# LEDMatrix.net
KiCad netlist of a schematic drawn in Altium Designer
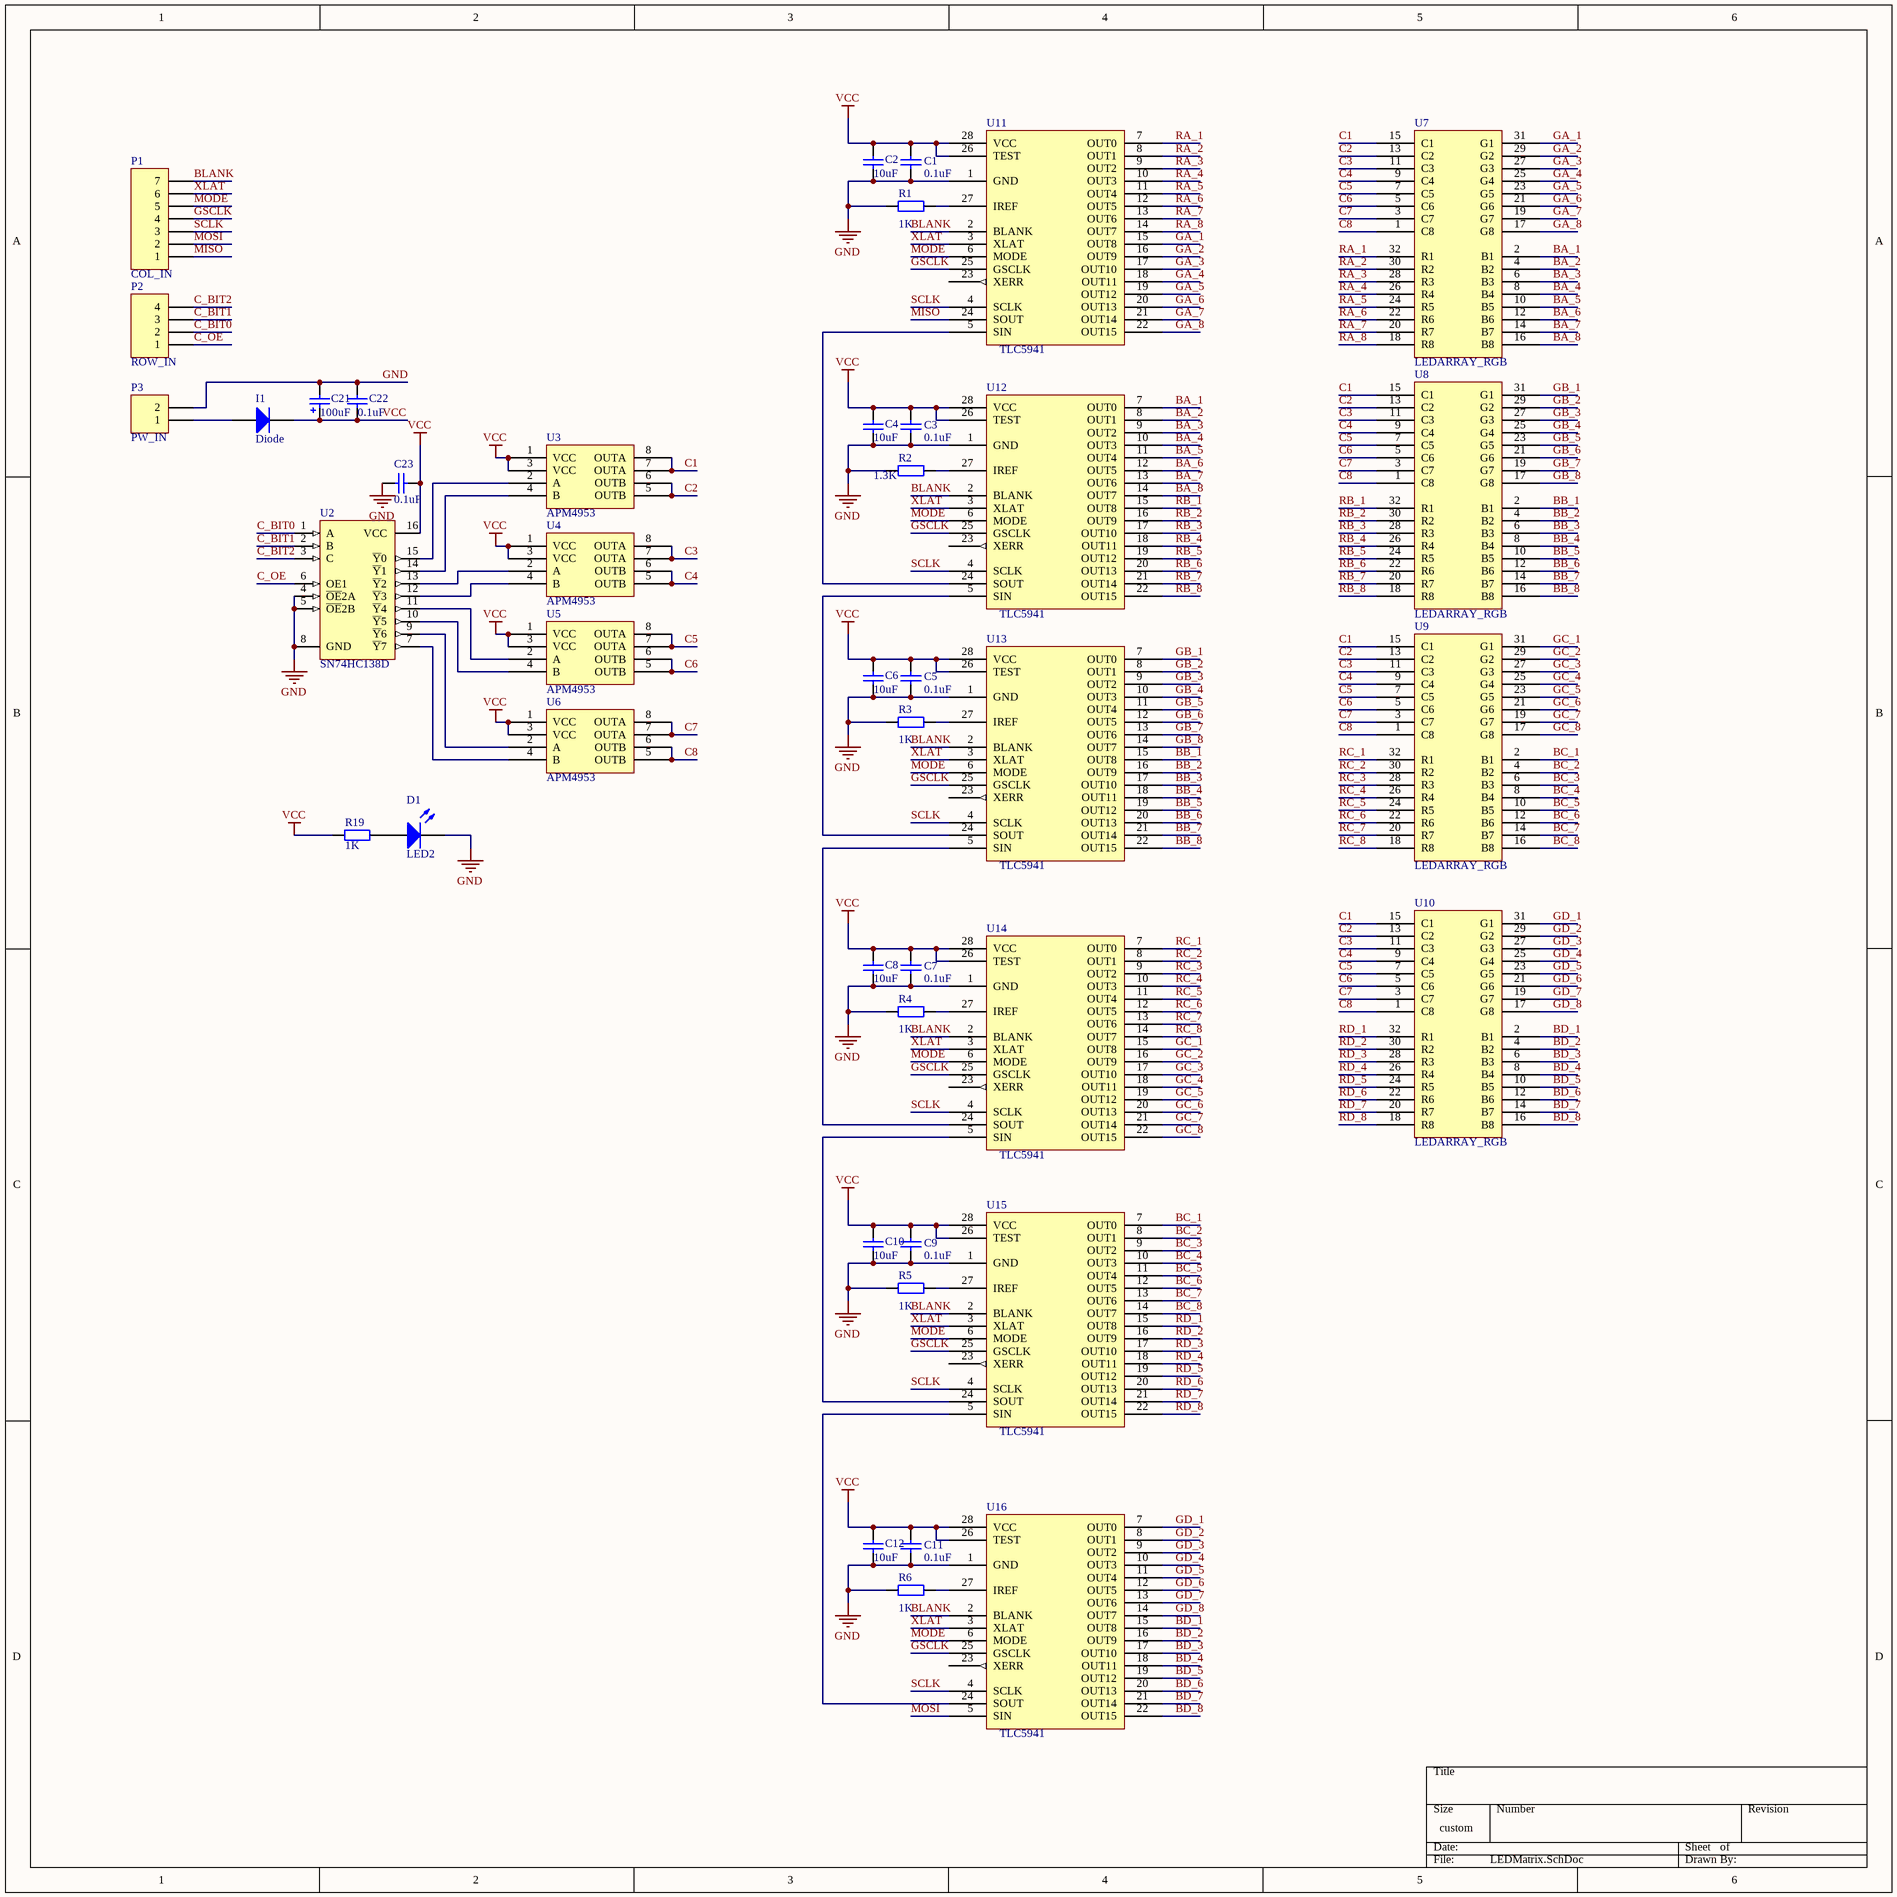
[diagram p0: LEDMatrix.SchDoc]

(export (version "E")
  (design (tool "Eeschema 10.0.6"))
  (components
    (comp (ref "C1")
      (value "0.1uF")
      (footprint "C-0805")
      (description "Capacitor")
      (fields (field (name "Comment") "Cap") (field (name "PUBLISHER") "Altium Limited"))
      (libsource (lib "Miscellaneous Devices") (part "Cap"))
    )
    (comp (ref "C2")
      (value "10uF")
      (footprint "C-0805")
      (description "Capacitor")
      (fields (field (name "Comment") "Cap") (field (name "PUBLISHER") "Altium Limited"))
      (libsource (lib "Miscellaneous Devices") (part "Cap"))
    )
    (comp (ref "C3")
      (value "0.1uF")
      (footprint "C-0805")
      (description "Capacitor")
      (fields (field (name "Comment") "Cap") (field (name "PUBLISHER") "Altium Limited"))
      (libsource (lib "Miscellaneous Devices") (part "Cap"))
    )
    (comp (ref "C4")
      (value "10uF")
      (footprint "C-0805")
      (description "Capacitor")
      (fields (field (name "Comment") "Cap") (field (name "PUBLISHER") "Altium Limited"))
      (libsource (lib "Miscellaneous Devices") (part "Cap"))
    )
    (comp (ref "C5")
      (value "0.1uF")
      (footprint "C-0805")
      (description "Capacitor")
      (fields (field (name "Comment") "Cap") (field (name "PUBLISHER") "Altium Limited"))
      (libsource (lib "Miscellaneous Devices") (part "Cap"))
    )
    (comp (ref "C6")
      (value "10uF")
      (footprint "C-0805")
      (description "Capacitor")
      (fields (field (name "Comment") "Cap") (field (name "PUBLISHER") "Altium Limited"))
      (libsource (lib "Miscellaneous Devices") (part "Cap"))
    )
    (comp (ref "C7")
      (value "0.1uF")
      (footprint "C-0805")
      (description "Capacitor")
      (fields (field (name "Comment") "Cap") (field (name "PUBLISHER") "Altium Limited"))
      (libsource (lib "Miscellaneous Devices") (part "Cap"))
    )
    (comp (ref "C8")
      (value "10uF")
      (footprint "C-0805")
      (description "Capacitor")
      (fields (field (name "Comment") "Cap") (field (name "PUBLISHER") "Altium Limited"))
      (libsource (lib "Miscellaneous Devices") (part "Cap"))
    )
    (comp (ref "C9")
      (value "0.1uF")
      (footprint "C-0805")
      (description "Capacitor")
      (fields (field (name "Comment") "Cap") (field (name "PUBLISHER") "Altium Limited"))
      (libsource (lib "Miscellaneous Devices") (part "Cap"))
    )
    (comp (ref "C10")
      (value "10uF")
      (footprint "C-0805")
      (description "Capacitor")
      (fields (field (name "Comment") "Cap") (field (name "PUBLISHER") "Altium Limited"))
      (libsource (lib "Miscellaneous Devices") (part "Cap"))
    )
    (comp (ref "C11")
      (value "0.1uF")
      (footprint "C-0805")
      (description "Capacitor")
      (fields (field (name "Comment") "Cap") (field (name "PUBLISHER") "Altium Limited"))
      (libsource (lib "Miscellaneous Devices") (part "Cap"))
    )
    (comp (ref "C12")
      (value "10uF")
      (footprint "C-0805")
      (description "Capacitor")
      (fields (field (name "Comment") "Cap") (field (name "PUBLISHER") "Altium Limited"))
      (libsource (lib "Miscellaneous Devices") (part "Cap"))
    )
    (comp (ref "C21")
      (value "100uF")
      (footprint "CAPAE-D")
      (description "Polarized Capacitor (Axial)")
      (fields (field (name "Comment") "Cap Pol2") (field (name "PUBLISHER") "Altium Limited"))
      (libsource (lib "Miscellaneous Devices") (part "Cap Pol2"))
    )
    (comp (ref "C22")
      (value "0.1uF")
      (footprint "C-0805")
      (description "Capacitor")
      (fields (field (name "Comment") "Cap") (field (name "PUBLISHER") "Altium Limited"))
      (libsource (lib "Miscellaneous Devices") (part "Cap"))
    )
    (comp (ref "C23")
      (value "0.1uF")
      (footprint "C-0805")
      (description "Capacitor")
      (fields (field (name "Comment") "Cap") (field (name "PUBLISHER") "Altium Limited"))
      (libsource (lib "Miscellaneous Devices") (part "Cap"))
    )
    (comp (ref "D1")
      (value "LED2")
      (footprint "LED-0805")
      (description "Typical RED, GREEN, YELLOW, AMBER GaAs LED")
      (fields (field (name "PUBLISHER") "Altium Limited"))
      (libsource (lib "Miscellaneous Devices") (part "LED2"))
    )
    (comp (ref "I1")
      (value "Diode")
      (footprint "D-SMA")
      (description "Default Diode")
      (fields (field (name "PUBLISHER") "Altium Limited"))
      (libsource (lib "Miscellaneous Devices") (part "Diode"))
    )
    (comp (ref "P1")
      (value "COL_IN")
      (footprint "HDR1X7")
      (description "Header, 7-Pin")
      (fields (field (name "PUBLISHER") "Altium Limited"))
      (libsource (lib "Miscellaneous Connectors") (part "Header 7"))
    )
    (comp (ref "P2")
      (value "ROW_IN")
      (footprint "HDR1X4")
      (description "Header, 4-Pin")
      (fields (field (name "PUBLISHER") "Altium Limited"))
      (libsource (lib "Miscellaneous Connectors") (part "Header 4"))
    )
    (comp (ref "P3")
      (value "PW_IN")
      (footprint "HDR1X2")
      (description "Header, 2-Pin")
      (fields (field (name "PUBLISHER") "Altium Limited"))
      (libsource (lib "Miscellaneous Connectors") (part "Header 2"))
    )
    (comp (ref "R1")
      (value "1K")
      (footprint "0805-1")
      (description "Resistor")
      (fields (field (name "Comment") "Res2") (field (name "PUBLISHER") "Altium Limited"))
      (libsource (lib "Miscellaneous Devices") (part "Res2"))
    )
    (comp (ref "R2")
      (value "1.3K")
      (footprint "0805-1")
      (description "Resistor")
      (fields (field (name "Comment") "Res2") (field (name "PUBLISHER") "Altium Limited"))
      (libsource (lib "Miscellaneous Devices") (part "Res2"))
    )
    (comp (ref "R3")
      (value "1K")
      (footprint "0805-1")
      (description "Resistor")
      (fields (field (name "Comment") "Res2") (field (name "PUBLISHER") "Altium Limited"))
      (libsource (lib "Miscellaneous Devices") (part "Res2"))
    )
    (comp (ref "R4")
      (value "1K")
      (footprint "0805-1")
      (description "Resistor")
      (fields (field (name "Comment") "Res2") (field (name "PUBLISHER") "Altium Limited"))
      (libsource (lib "Miscellaneous Devices") (part "Res2"))
    )
    (comp (ref "R5")
      (value "1K")
      (footprint "0805-1")
      (description "Resistor")
      (fields (field (name "Comment") "Res2") (field (name "PUBLISHER") "Altium Limited"))
      (libsource (lib "Miscellaneous Devices") (part "Res2"))
    )
    (comp (ref "R6")
      (value "1K")
      (footprint "0805-1")
      (description "Resistor")
      (fields (field (name "Comment") "Res2") (field (name "PUBLISHER") "Altium Limited"))
      (libsource (lib "Miscellaneous Devices") (part "Res2"))
    )
    (comp (ref "R19")
      (value "1K")
      (footprint "0805-1")
      (description "Resistor")
      (fields (field (name "Comment") "Res2") (field (name "PUBLISHER") "Altium Limited"))
      (libsource (lib "") (part "Res2_1"))
    )
    (comp (ref "U2")
      (value "SN74HC138D")
      (footprint "SOIC-16")
      (description "3-Line to 8-Line Decoder / Demultiplexer")
      (fields (field (name "PUBLISHER") "Altium Limited"))
      (libsource (lib "TI Logic Decoder Demux") (part "SN74HC138D"))
    )
    (comp (ref "U3") (value "APM4953") (footprint "SOIC-8") (libsource (lib "Schlib1") (part "APM4953")))
    (comp (ref "U4") (value "APM4953") (footprint "SOIC-8") (libsource (lib "Schlib1") (part "APM4953")))
    (comp (ref "U5") (value "APM4953") (footprint "SOIC-8") (libsource (lib "Schlib1") (part "APM4953")))
    (comp (ref "U6") (value "APM4953") (footprint "SOIC-8") (libsource (lib "Schlib1") (part "APM4953")))
    (comp (ref "U7")
      (value "LEDARRAY_RGB")
      (footprint "DIP32")
      (libsource (lib "Schlib1") (part "LEDARRAY_RGB"))
    )
    (comp (ref "U8")
      (value "LEDARRAY_RGB")
      (footprint "DIP32")
      (libsource (lib "Schlib1") (part "LEDARRAY_RGB"))
    )
    (comp (ref "U9")
      (value "LEDARRAY_RGB")
      (footprint "DIP32")
      (libsource (lib "Schlib1") (part "LEDARRAY_RGB"))
    )
    (comp (ref "U10")
      (value "LEDARRAY_RGB")
      (footprint "DIP32")
      (libsource (lib "Schlib1") (part "LEDARRAY_RGB"))
    )
    (comp (ref "U11") (value "TLC5941") (footprint "TSOP28_N") (libsource (lib "Schlib1") (part "TLC5941")))
    (comp (ref "U12") (value "TLC5941") (footprint "TSOP28_N") (libsource (lib "Schlib1") (part "TLC5941")))
    (comp (ref "U13") (value "TLC5941") (footprint "TSOP28_N") (libsource (lib "Schlib1") (part "TLC5941")))
    (comp (ref "U14") (value "TLC5941") (footprint "TSOP28_N") (libsource (lib "Schlib1") (part "TLC5941")))
    (comp (ref "U15") (value "TLC5941") (footprint "TSOP28_N") (libsource (lib "Schlib1") (part "TLC5941")))
    (comp (ref "U16") (value "TLC5941") (footprint "TSOP28_N") (libsource (lib "Schlib1") (part "TLC5941")))
  )
  (nets
    (net (code "1") (name "/BA_1") (class "Default")
      (node (ref "U12") (pin "7") (pinfunction "OUT0_7") (pintype "passive"))
      (node (ref "U7") (pin "2") (pinfunction "B1_2") (pintype "passive"))
    )
    (net (code "2") (name "/BA_2") (class "Default")
      (node (ref "U12") (pin "8") (pinfunction "OUT1_8") (pintype "passive"))
      (node (ref "U7") (pin "4") (pinfunction "B2_4") (pintype "passive"))
    )
    (net (code "3") (name "/BA_3") (class "Default")
      (node (ref "U12") (pin "9") (pinfunction "OUT2_9") (pintype "passive"))
      (node (ref "U7") (pin "6") (pinfunction "B3_6") (pintype "passive"))
    )
    (net (code "4") (name "/BA_4") (class "Default")
      (node (ref "U12") (pin "10") (pinfunction "OUT3_10") (pintype "passive"))
      (node (ref "U7") (pin "8") (pinfunction "B4_8") (pintype "passive"))
    )
    (net (code "5") (name "/BA_5") (class "Default")
      (node (ref "U12") (pin "11") (pinfunction "OUT4_11") (pintype "passive"))
      (node (ref "U7") (pin "10") (pinfunction "B5_10") (pintype "passive"))
    )
    (net (code "6") (name "/BA_6") (class "Default")
      (node (ref "U12") (pin "12") (pinfunction "OUT5_12") (pintype "passive"))
      (node (ref "U7") (pin "12") (pinfunction "B6_12") (pintype "passive"))
    )
    (net (code "7") (name "/BA_7") (class "Default")
      (node (ref "U12") (pin "13") (pinfunction "OUT6_13") (pintype "passive"))
      (node (ref "U7") (pin "14") (pinfunction "B7_14") (pintype "passive"))
    )
    (net (code "8") (name "/BA_8") (class "Default")
      (node (ref "U12") (pin "14") (pinfunction "OUT7_14") (pintype "passive"))
      (node (ref "U7") (pin "16") (pinfunction "B8_16") (pintype "passive"))
    )
    (net (code "9") (name "/BB_1") (class "Default")
      (node (ref "U13") (pin "15") (pinfunction "OUT8_15") (pintype "passive"))
      (node (ref "U8") (pin "2") (pinfunction "B1_2") (pintype "passive"))
    )
    (net (code "10") (name "/BB_2") (class "Default")
      (node (ref "U13") (pin "16") (pinfunction "OUT9_16") (pintype "passive"))
      (node (ref "U8") (pin "4") (pinfunction "B2_4") (pintype "passive"))
    )
    (net (code "11") (name "/BB_3") (class "Default")
      (node (ref "U13") (pin "17") (pinfunction "OUT10_17") (pintype "passive"))
      (node (ref "U8") (pin "6") (pinfunction "B3_6") (pintype "passive"))
    )
    (net (code "12") (name "/BB_4") (class "Default")
      (node (ref "U13") (pin "18") (pinfunction "OUT11_18") (pintype "passive"))
      (node (ref "U8") (pin "8") (pinfunction "B4_8") (pintype "passive"))
    )
    (net (code "13") (name "/BB_5") (class "Default")
      (node (ref "U13") (pin "19") (pinfunction "OUT12_19") (pintype "passive"))
      (node (ref "U8") (pin "10") (pinfunction "B5_10") (pintype "passive"))
    )
    (net (code "14") (name "/BB_6") (class "Default")
      (node (ref "U13") (pin "20") (pinfunction "OUT13_20") (pintype "passive"))
      (node (ref "U8") (pin "12") (pinfunction "B6_12") (pintype "passive"))
    )
    (net (code "15") (name "/BB_7") (class "Default")
      (node (ref "U13") (pin "21") (pinfunction "OUT14_21") (pintype "passive"))
      (node (ref "U8") (pin "14") (pinfunction "B7_14") (pintype "passive"))
    )
    (net (code "16") (name "/BB_8") (class "Default")
      (node (ref "U13") (pin "22") (pinfunction "OUT15_22") (pintype "passive"))
      (node (ref "U8") (pin "16") (pinfunction "B8_16") (pintype "passive"))
    )
    (net (code "17") (name "/BC_1") (class "Default")
      (node (ref "U15") (pin "7") (pinfunction "OUT0_7") (pintype "passive"))
      (node (ref "U9") (pin "2") (pinfunction "B1_2") (pintype "passive"))
    )
    (net (code "18") (name "/BC_2") (class "Default")
      (node (ref "U15") (pin "8") (pinfunction "OUT1_8") (pintype "passive"))
      (node (ref "U9") (pin "4") (pinfunction "B2_4") (pintype "passive"))
    )
    (net (code "19") (name "/BC_3") (class "Default")
      (node (ref "U15") (pin "9") (pinfunction "OUT2_9") (pintype "passive"))
      (node (ref "U9") (pin "6") (pinfunction "B3_6") (pintype "passive"))
    )
    (net (code "20") (name "/BC_4") (class "Default")
      (node (ref "U15") (pin "10") (pinfunction "OUT3_10") (pintype "passive"))
      (node (ref "U9") (pin "8") (pinfunction "B4_8") (pintype "passive"))
    )
    (net (code "21") (name "/BC_5") (class "Default")
      (node (ref "U15") (pin "11") (pinfunction "OUT4_11") (pintype "passive"))
      (node (ref "U9") (pin "10") (pinfunction "B5_10") (pintype "passive"))
    )
    (net (code "22") (name "/BC_6") (class "Default")
      (node (ref "U15") (pin "12") (pinfunction "OUT5_12") (pintype "passive"))
      (node (ref "U9") (pin "12") (pinfunction "B6_12") (pintype "passive"))
    )
    (net (code "23") (name "/BC_7") (class "Default")
      (node (ref "U15") (pin "13") (pinfunction "OUT6_13") (pintype "passive"))
      (node (ref "U9") (pin "14") (pinfunction "B7_14") (pintype "passive"))
    )
    (net (code "24") (name "/BC_8") (class "Default")
      (node (ref "U15") (pin "14") (pinfunction "OUT7_14") (pintype "passive"))
      (node (ref "U9") (pin "16") (pinfunction "B8_16") (pintype "passive"))
    )
    (net (code "25") (name "/BD_1") (class "Default")
      (node (ref "U10") (pin "2") (pinfunction "B1_2") (pintype "passive"))
      (node (ref "U16") (pin "15") (pinfunction "OUT8_15") (pintype "passive"))
    )
    (net (code "26") (name "/BD_2") (class "Default")
      (node (ref "U10") (pin "4") (pinfunction "B2_4") (pintype "passive"))
      (node (ref "U16") (pin "16") (pinfunction "OUT9_16") (pintype "passive"))
    )
    (net (code "27") (name "/BD_3") (class "Default")
      (node (ref "U10") (pin "6") (pinfunction "B3_6") (pintype "passive"))
      (node (ref "U16") (pin "17") (pinfunction "OUT10_17") (pintype "passive"))
    )
    (net (code "28") (name "/BD_4") (class "Default")
      (node (ref "U10") (pin "8") (pinfunction "B4_8") (pintype "passive"))
      (node (ref "U16") (pin "18") (pinfunction "OUT11_18") (pintype "passive"))
    )
    (net (code "29") (name "/BD_5") (class "Default")
      (node (ref "U10") (pin "10") (pinfunction "B5_10") (pintype "passive"))
      (node (ref "U16") (pin "19") (pinfunction "OUT12_19") (pintype "passive"))
    )
    (net (code "30") (name "/BD_6") (class "Default")
      (node (ref "U10") (pin "12") (pinfunction "B6_12") (pintype "passive"))
      (node (ref "U16") (pin "20") (pinfunction "OUT13_20") (pintype "passive"))
    )
    (net (code "31") (name "/BD_7") (class "Default")
      (node (ref "U10") (pin "14") (pinfunction "B7_14") (pintype "passive"))
      (node (ref "U16") (pin "21") (pinfunction "OUT14_21") (pintype "passive"))
    )
    (net (code "32") (name "/BD_8") (class "Default")
      (node (ref "U10") (pin "16") (pinfunction "B8_16") (pintype "passive"))
      (node (ref "U16") (pin "22") (pinfunction "OUT15_22") (pintype "passive"))
    )
    (net (code "33") (name "/BLANK") (class "Default")
      (node (ref "P1") (pin "7") (pinfunction "7_7") (pintype "passive"))
      (node (ref "U11") (pin "2") (pinfunction "BLANK_2") (pintype "passive"))
      (node (ref "U12") (pin "2") (pinfunction "BLANK_2") (pintype "passive"))
      (node (ref "U13") (pin "2") (pinfunction "BLANK_2") (pintype "passive"))
      (node (ref "U14") (pin "2") (pinfunction "BLANK_2") (pintype "passive"))
      (node (ref "U15") (pin "2") (pinfunction "BLANK_2") (pintype "passive"))
      (node (ref "U16") (pin "2") (pinfunction "BLANK_2") (pintype "passive"))
    )
    (net (code "34") (name "/C1") (class "Default")
      (node (ref "U10") (pin "15") (pinfunction "C1_15") (pintype "passive"))
      (node (ref "U3") (pin "7") (pinfunction "OUTA_7") (pintype "passive"))
      (node (ref "U3") (pin "8") (pinfunction "OUTA_8") (pintype "passive"))
      (node (ref "U7") (pin "15") (pinfunction "C1_15") (pintype "passive"))
      (node (ref "U8") (pin "15") (pinfunction "C1_15") (pintype "passive"))
      (node (ref "U9") (pin "15") (pinfunction "C1_15") (pintype "passive"))
    )
    (net (code "35") (name "/C2") (class "Default")
      (node (ref "U10") (pin "13") (pinfunction "C2_13") (pintype "passive"))
      (node (ref "U3") (pin "5") (pinfunction "OUTB_5") (pintype "passive"))
      (node (ref "U3") (pin "6") (pinfunction "OUTB_6") (pintype "passive"))
      (node (ref "U7") (pin "13") (pinfunction "C2_13") (pintype "passive"))
      (node (ref "U8") (pin "13") (pinfunction "C2_13") (pintype "passive"))
      (node (ref "U9") (pin "13") (pinfunction "C2_13") (pintype "passive"))
    )
    (net (code "36") (name "/C3") (class "Default")
      (node (ref "U10") (pin "11") (pinfunction "C3_11") (pintype "passive"))
      (node (ref "U4") (pin "7") (pinfunction "OUTA_7") (pintype "passive"))
      (node (ref "U4") (pin "8") (pinfunction "OUTA_8") (pintype "passive"))
      (node (ref "U7") (pin "11") (pinfunction "C3_11") (pintype "passive"))
      (node (ref "U8") (pin "11") (pinfunction "C3_11") (pintype "passive"))
      (node (ref "U9") (pin "11") (pinfunction "C3_11") (pintype "passive"))
    )
    (net (code "37") (name "/C4") (class "Default")
      (node (ref "U10") (pin "9") (pinfunction "C4_9") (pintype "passive"))
      (node (ref "U4") (pin "5") (pinfunction "OUTB_5") (pintype "passive"))
      (node (ref "U4") (pin "6") (pinfunction "OUTB_6") (pintype "passive"))
      (node (ref "U7") (pin "9") (pinfunction "C4_9") (pintype "passive"))
      (node (ref "U8") (pin "9") (pinfunction "C4_9") (pintype "passive"))
      (node (ref "U9") (pin "9") (pinfunction "C4_9") (pintype "passive"))
    )
    (net (code "38") (name "/C5") (class "Default")
      (node (ref "U10") (pin "7") (pinfunction "C5_7") (pintype "passive"))
      (node (ref "U5") (pin "7") (pinfunction "OUTA_7") (pintype "passive"))
      (node (ref "U5") (pin "8") (pinfunction "OUTA_8") (pintype "passive"))
      (node (ref "U7") (pin "7") (pinfunction "C5_7") (pintype "passive"))
      (node (ref "U8") (pin "7") (pinfunction "C5_7") (pintype "passive"))
      (node (ref "U9") (pin "7") (pinfunction "C5_7") (pintype "passive"))
    )
    (net (code "39") (name "/C6") (class "Default")
      (node (ref "U10") (pin "5") (pinfunction "C6_5") (pintype "passive"))
      (node (ref "U5") (pin "5") (pinfunction "OUTB_5") (pintype "passive"))
      (node (ref "U5") (pin "6") (pinfunction "OUTB_6") (pintype "passive"))
      (node (ref "U7") (pin "5") (pinfunction "C6_5") (pintype "passive"))
      (node (ref "U8") (pin "5") (pinfunction "C6_5") (pintype "passive"))
      (node (ref "U9") (pin "5") (pinfunction "C6_5") (pintype "passive"))
    )
    (net (code "40") (name "/C7") (class "Default")
      (node (ref "U10") (pin "3") (pinfunction "C7_3") (pintype "passive"))
      (node (ref "U6") (pin "7") (pinfunction "OUTA_7") (pintype "passive"))
      (node (ref "U6") (pin "8") (pinfunction "OUTA_8") (pintype "passive"))
      (node (ref "U7") (pin "3") (pinfunction "C7_3") (pintype "passive"))
      (node (ref "U8") (pin "3") (pinfunction "C7_3") (pintype "passive"))
      (node (ref "U9") (pin "3") (pinfunction "C7_3") (pintype "passive"))
    )
    (net (code "41") (name "/C8") (class "Default")
      (node (ref "U10") (pin "1") (pinfunction "C8_1") (pintype "passive"))
      (node (ref "U6") (pin "5") (pinfunction "OUTB_5") (pintype "passive"))
      (node (ref "U6") (pin "6") (pinfunction "OUTB_6") (pintype "passive"))
      (node (ref "U7") (pin "1") (pinfunction "C8_1") (pintype "passive"))
      (node (ref "U8") (pin "1") (pinfunction "C8_1") (pintype "passive"))
      (node (ref "U9") (pin "1") (pinfunction "C8_1") (pintype "passive"))
    )
    (net (code "42") (name "/C_BIT0") (class "Default")
      (node (ref "P2") (pin "2") (pinfunction "2_2") (pintype "passive"))
      (node (ref "U2") (pin "1") (pinfunction "A_1") (pintype "input"))
    )
    (net (code "43") (name "/C_BIT1") (class "Default")
      (node (ref "P2") (pin "3") (pinfunction "3_3") (pintype "passive"))
      (node (ref "U2") (pin "2") (pinfunction "B_2") (pintype "input"))
    )
    (net (code "44") (name "/C_BIT2") (class "Default")
      (node (ref "P2") (pin "4") (pinfunction "4_4") (pintype "passive"))
      (node (ref "U2") (pin "3") (pinfunction "C_3") (pintype "input"))
    )
    (net (code "45") (name "/C_OE") (class "Default")
      (node (ref "P2") (pin "1") (pinfunction "1_1") (pintype "passive"))
      (node (ref "U2") (pin "6") (pinfunction "OE1_6") (pintype "input"))
    )
    (net (code "46") (name "/GA_1") (class "Default")
      (node (ref "U11") (pin "15") (pinfunction "OUT8_15") (pintype "passive"))
      (node (ref "U7") (pin "31") (pinfunction "G1_31") (pintype "passive"))
    )
    (net (code "47") (name "/GA_2") (class "Default")
      (node (ref "U11") (pin "16") (pinfunction "OUT9_16") (pintype "passive"))
      (node (ref "U7") (pin "29") (pinfunction "G2_29") (pintype "passive"))
    )
    (net (code "48") (name "/GA_3") (class "Default")
      (node (ref "U11") (pin "17") (pinfunction "OUT10_17") (pintype "passive"))
      (node (ref "U7") (pin "27") (pinfunction "G3_27") (pintype "passive"))
    )
    (net (code "49") (name "/GA_4") (class "Default")
      (node (ref "U11") (pin "18") (pinfunction "OUT11_18") (pintype "passive"))
      (node (ref "U7") (pin "25") (pinfunction "G4_25") (pintype "passive"))
    )
    (net (code "50") (name "/GA_5") (class "Default")
      (node (ref "U11") (pin "19") (pinfunction "OUT12_19") (pintype "passive"))
      (node (ref "U7") (pin "23") (pinfunction "G5_23") (pintype "passive"))
    )
    (net (code "51") (name "/GA_6") (class "Default")
      (node (ref "U11") (pin "20") (pinfunction "OUT13_20") (pintype "passive"))
      (node (ref "U7") (pin "21") (pinfunction "G6_21") (pintype "passive"))
    )
    (net (code "52") (name "/GA_7") (class "Default")
      (node (ref "U11") (pin "21") (pinfunction "OUT14_21") (pintype "passive"))
      (node (ref "U7") (pin "19") (pinfunction "G7_19") (pintype "passive"))
    )
    (net (code "53") (name "/GA_8") (class "Default")
      (node (ref "U11") (pin "22") (pinfunction "OUT15_22") (pintype "passive"))
      (node (ref "U7") (pin "17") (pinfunction "G8_17") (pintype "passive"))
    )
    (net (code "54") (name "/GB_1") (class "Default")
      (node (ref "U13") (pin "7") (pinfunction "OUT0_7") (pintype "passive"))
      (node (ref "U8") (pin "31") (pinfunction "G1_31") (pintype "passive"))
    )
    (net (code "55") (name "/GB_2") (class "Default")
      (node (ref "U13") (pin "8") (pinfunction "OUT1_8") (pintype "passive"))
      (node (ref "U8") (pin "29") (pinfunction "G2_29") (pintype "passive"))
    )
    (net (code "56") (name "/GB_3") (class "Default")
      (node (ref "U13") (pin "9") (pinfunction "OUT2_9") (pintype "passive"))
      (node (ref "U8") (pin "27") (pinfunction "G3_27") (pintype "passive"))
    )
    (net (code "57") (name "/GB_4") (class "Default")
      (node (ref "U13") (pin "10") (pinfunction "OUT3_10") (pintype "passive"))
      (node (ref "U8") (pin "25") (pinfunction "G4_25") (pintype "passive"))
    )
    (net (code "58") (name "/GB_5") (class "Default")
      (node (ref "U13") (pin "11") (pinfunction "OUT4_11") (pintype "passive"))
      (node (ref "U8") (pin "23") (pinfunction "G5_23") (pintype "passive"))
    )
    (net (code "59") (name "/GB_6") (class "Default")
      (node (ref "U13") (pin "12") (pinfunction "OUT5_12") (pintype "passive"))
      (node (ref "U8") (pin "21") (pinfunction "G6_21") (pintype "passive"))
    )
    (net (code "60") (name "/GB_7") (class "Default")
      (node (ref "U13") (pin "13") (pinfunction "OUT6_13") (pintype "passive"))
      (node (ref "U8") (pin "19") (pinfunction "G7_19") (pintype "passive"))
    )
    (net (code "61") (name "/GB_8") (class "Default")
      (node (ref "U13") (pin "14") (pinfunction "OUT7_14") (pintype "passive"))
      (node (ref "U8") (pin "17") (pinfunction "G8_17") (pintype "passive"))
    )
    (net (code "62") (name "/GC_1") (class "Default")
      (node (ref "U14") (pin "15") (pinfunction "OUT8_15") (pintype "passive"))
      (node (ref "U9") (pin "31") (pinfunction "G1_31") (pintype "passive"))
    )
    (net (code "63") (name "/GC_2") (class "Default")
      (node (ref "U14") (pin "16") (pinfunction "OUT9_16") (pintype "passive"))
      (node (ref "U9") (pin "29") (pinfunction "G2_29") (pintype "passive"))
    )
    (net (code "64") (name "/GC_3") (class "Default")
      (node (ref "U14") (pin "17") (pinfunction "OUT10_17") (pintype "passive"))
      (node (ref "U9") (pin "27") (pinfunction "G3_27") (pintype "passive"))
    )
    (net (code "65") (name "/GC_4") (class "Default")
      (node (ref "U14") (pin "18") (pinfunction "OUT11_18") (pintype "passive"))
      (node (ref "U9") (pin "25") (pinfunction "G4_25") (pintype "passive"))
    )
    (net (code "66") (name "/GC_5") (class "Default")
      (node (ref "U14") (pin "19") (pinfunction "OUT12_19") (pintype "passive"))
      (node (ref "U9") (pin "23") (pinfunction "G5_23") (pintype "passive"))
    )
    (net (code "67") (name "/GC_6") (class "Default")
      (node (ref "U14") (pin "20") (pinfunction "OUT13_20") (pintype "passive"))
      (node (ref "U9") (pin "21") (pinfunction "G6_21") (pintype "passive"))
    )
    (net (code "68") (name "/GC_7") (class "Default")
      (node (ref "U14") (pin "21") (pinfunction "OUT14_21") (pintype "passive"))
      (node (ref "U9") (pin "19") (pinfunction "G7_19") (pintype "passive"))
    )
    (net (code "69") (name "/GC_8") (class "Default")
      (node (ref "U14") (pin "22") (pinfunction "OUT15_22") (pintype "passive"))
      (node (ref "U9") (pin "17") (pinfunction "G8_17") (pintype "passive"))
    )
    (net (code "70") (name "/GD_1") (class "Default")
      (node (ref "U10") (pin "31") (pinfunction "G1_31") (pintype "passive"))
      (node (ref "U16") (pin "7") (pinfunction "OUT0_7") (pintype "passive"))
    )
    (net (code "71") (name "/GD_2") (class "Default")
      (node (ref "U10") (pin "29") (pinfunction "G2_29") (pintype "passive"))
      (node (ref "U16") (pin "8") (pinfunction "OUT1_8") (pintype "passive"))
    )
    (net (code "72") (name "/GD_3") (class "Default")
      (node (ref "U10") (pin "27") (pinfunction "G3_27") (pintype "passive"))
      (node (ref "U16") (pin "9") (pinfunction "OUT2_9") (pintype "passive"))
    )
    (net (code "73") (name "/GD_4") (class "Default")
      (node (ref "U10") (pin "25") (pinfunction "G4_25") (pintype "passive"))
      (node (ref "U16") (pin "10") (pinfunction "OUT3_10") (pintype "passive"))
    )
    (net (code "74") (name "/GD_5") (class "Default")
      (node (ref "U10") (pin "23") (pinfunction "G5_23") (pintype "passive"))
      (node (ref "U16") (pin "11") (pinfunction "OUT4_11") (pintype "passive"))
    )
    (net (code "75") (name "/GD_6") (class "Default")
      (node (ref "U10") (pin "21") (pinfunction "G6_21") (pintype "passive"))
      (node (ref "U16") (pin "12") (pinfunction "OUT5_12") (pintype "passive"))
    )
    (net (code "76") (name "/GD_7") (class "Default")
      (node (ref "U10") (pin "19") (pinfunction "G7_19") (pintype "passive"))
      (node (ref "U16") (pin "13") (pinfunction "OUT6_13") (pintype "passive"))
    )
    (net (code "77") (name "/GD_8") (class "Default")
      (node (ref "U10") (pin "17") (pinfunction "G8_17") (pintype "passive"))
      (node (ref "U16") (pin "14") (pinfunction "OUT7_14") (pintype "passive"))
    )
    (net (code "78") (name "/GSCLK") (class "Default")
      (node (ref "P1") (pin "4") (pinfunction "4_4") (pintype "passive"))
      (node (ref "U11") (pin "25") (pinfunction "GSCLK_25") (pintype "passive"))
      (node (ref "U12") (pin "25") (pinfunction "GSCLK_25") (pintype "passive"))
      (node (ref "U13") (pin "25") (pinfunction "GSCLK_25") (pintype "passive"))
      (node (ref "U14") (pin "25") (pinfunction "GSCLK_25") (pintype "passive"))
      (node (ref "U15") (pin "25") (pinfunction "GSCLK_25") (pintype "passive"))
      (node (ref "U16") (pin "25") (pinfunction "GSCLK_25") (pintype "passive"))
    )
    (net (code "79") (name "/MISO") (class "Default")
      (node (ref "P1") (pin "1") (pinfunction "1_1") (pintype "passive"))
      (node (ref "U11") (pin "24") (pinfunction "SOUT_24") (pintype "passive"))
    )
    (net (code "80") (name "/MODE") (class "Default")
      (node (ref "P1") (pin "5") (pinfunction "5_5") (pintype "passive"))
      (node (ref "U11") (pin "6") (pinfunction "MODE_6") (pintype "passive"))
      (node (ref "U12") (pin "6") (pinfunction "MODE_6") (pintype "passive"))
      (node (ref "U13") (pin "6") (pinfunction "MODE_6") (pintype "passive"))
      (node (ref "U14") (pin "6") (pinfunction "MODE_6") (pintype "passive"))
      (node (ref "U15") (pin "6") (pinfunction "MODE_6") (pintype "passive"))
      (node (ref "U16") (pin "6") (pinfunction "MODE_6") (pintype "passive"))
    )
    (net (code "81") (name "/MOSI") (class "Default")
      (node (ref "P1") (pin "2") (pinfunction "2_2") (pintype "passive"))
      (node (ref "U16") (pin "5") (pinfunction "SIN_5") (pintype "passive"))
    )
    (net (code "82") (name "/RA_1") (class "Default")
      (node (ref "U11") (pin "7") (pinfunction "OUT0_7") (pintype "passive"))
      (node (ref "U7") (pin "32") (pinfunction "R1_32") (pintype "passive"))
    )
    (net (code "83") (name "/RA_2") (class "Default")
      (node (ref "U11") (pin "8") (pinfunction "OUT1_8") (pintype "passive"))
      (node (ref "U7") (pin "30") (pinfunction "R2_30") (pintype "passive"))
    )
    (net (code "84") (name "/RA_3") (class "Default")
      (node (ref "U11") (pin "9") (pinfunction "OUT2_9") (pintype "passive"))
      (node (ref "U7") (pin "28") (pinfunction "R3_28") (pintype "passive"))
    )
    (net (code "85") (name "/RA_4") (class "Default")
      (node (ref "U11") (pin "10") (pinfunction "OUT3_10") (pintype "passive"))
      (node (ref "U7") (pin "26") (pinfunction "R4_26") (pintype "passive"))
    )
    (net (code "86") (name "/RA_5") (class "Default")
      (node (ref "U11") (pin "11") (pinfunction "OUT4_11") (pintype "passive"))
      (node (ref "U7") (pin "24") (pinfunction "R5_24") (pintype "passive"))
    )
    (net (code "87") (name "/RA_6") (class "Default")
      (node (ref "U11") (pin "12") (pinfunction "OUT5_12") (pintype "passive"))
      (node (ref "U7") (pin "22") (pinfunction "R6_22") (pintype "passive"))
    )
    (net (code "88") (name "/RA_7") (class "Default")
      (node (ref "U11") (pin "13") (pinfunction "OUT6_13") (pintype "passive"))
      (node (ref "U7") (pin "20") (pinfunction "R7_20") (pintype "passive"))
    )
    (net (code "89") (name "/RA_8") (class "Default")
      (node (ref "U11") (pin "14") (pinfunction "OUT7_14") (pintype "passive"))
      (node (ref "U7") (pin "18") (pinfunction "R8_18") (pintype "passive"))
    )
    (net (code "90") (name "/RB_1") (class "Default")
      (node (ref "U12") (pin "15") (pinfunction "OUT8_15") (pintype "passive"))
      (node (ref "U8") (pin "32") (pinfunction "R1_32") (pintype "passive"))
    )
    (net (code "91") (name "/RB_2") (class "Default")
      (node (ref "U12") (pin "16") (pinfunction "OUT9_16") (pintype "passive"))
      (node (ref "U8") (pin "30") (pinfunction "R2_30") (pintype "passive"))
    )
    (net (code "92") (name "/RB_3") (class "Default")
      (node (ref "U12") (pin "17") (pinfunction "OUT10_17") (pintype "passive"))
      (node (ref "U8") (pin "28") (pinfunction "R3_28") (pintype "passive"))
    )
    (net (code "93") (name "/RB_4") (class "Default")
      (node (ref "U12") (pin "18") (pinfunction "OUT11_18") (pintype "passive"))
      (node (ref "U8") (pin "26") (pinfunction "R4_26") (pintype "passive"))
    )
    (net (code "94") (name "/RB_5") (class "Default")
      (node (ref "U12") (pin "19") (pinfunction "OUT12_19") (pintype "passive"))
      (node (ref "U8") (pin "24") (pinfunction "R5_24") (pintype "passive"))
    )
    (net (code "95") (name "/RB_6") (class "Default")
      (node (ref "U12") (pin "20") (pinfunction "OUT13_20") (pintype "passive"))
      (node (ref "U8") (pin "22") (pinfunction "R6_22") (pintype "passive"))
    )
    (net (code "96") (name "/RB_7") (class "Default")
      (node (ref "U12") (pin "21") (pinfunction "OUT14_21") (pintype "passive"))
      (node (ref "U8") (pin "20") (pinfunction "R7_20") (pintype "passive"))
    )
    (net (code "97") (name "/RB_8") (class "Default")
      (node (ref "U12") (pin "22") (pinfunction "OUT15_22") (pintype "passive"))
      (node (ref "U8") (pin "18") (pinfunction "R8_18") (pintype "passive"))
    )
    (net (code "98") (name "/RC_1") (class "Default")
      (node (ref "U14") (pin "7") (pinfunction "OUT0_7") (pintype "passive"))
      (node (ref "U9") (pin "32") (pinfunction "R1_32") (pintype "passive"))
    )
    (net (code "99") (name "/RC_2") (class "Default")
      (node (ref "U14") (pin "8") (pinfunction "OUT1_8") (pintype "passive"))
      (node (ref "U9") (pin "30") (pinfunction "R2_30") (pintype "passive"))
    )
    (net (code "100") (name "/RC_3") (class "Default")
      (node (ref "U14") (pin "9") (pinfunction "OUT2_9") (pintype "passive"))
      (node (ref "U9") (pin "28") (pinfunction "R3_28") (pintype "passive"))
    )
    (net (code "101") (name "/RC_4") (class "Default")
      (node (ref "U14") (pin "10") (pinfunction "OUT3_10") (pintype "passive"))
      (node (ref "U9") (pin "26") (pinfunction "R4_26") (pintype "passive"))
    )
    (net (code "102") (name "/RC_5") (class "Default")
      (node (ref "U14") (pin "11") (pinfunction "OUT4_11") (pintype "passive"))
      (node (ref "U9") (pin "24") (pinfunction "R5_24") (pintype "passive"))
    )
    (net (code "103") (name "/RC_6") (class "Default")
      (node (ref "U14") (pin "12") (pinfunction "OUT5_12") (pintype "passive"))
      (node (ref "U9") (pin "22") (pinfunction "R6_22") (pintype "passive"))
    )
    (net (code "104") (name "/RC_7") (class "Default")
      (node (ref "U14") (pin "13") (pinfunction "OUT6_13") (pintype "passive"))
      (node (ref "U9") (pin "20") (pinfunction "R7_20") (pintype "passive"))
    )
    (net (code "105") (name "/RC_8") (class "Default")
      (node (ref "U14") (pin "14") (pinfunction "OUT7_14") (pintype "passive"))
      (node (ref "U9") (pin "18") (pinfunction "R8_18") (pintype "passive"))
    )
    (net (code "106") (name "/RD_1") (class "Default")
      (node (ref "U10") (pin "32") (pinfunction "R1_32") (pintype "passive"))
      (node (ref "U15") (pin "15") (pinfunction "OUT8_15") (pintype "passive"))
    )
    (net (code "107") (name "/RD_2") (class "Default")
      (node (ref "U10") (pin "30") (pinfunction "R2_30") (pintype "passive"))
      (node (ref "U15") (pin "16") (pinfunction "OUT9_16") (pintype "passive"))
    )
    (net (code "108") (name "/RD_3") (class "Default")
      (node (ref "U10") (pin "28") (pinfunction "R3_28") (pintype "passive"))
      (node (ref "U15") (pin "17") (pinfunction "OUT10_17") (pintype "passive"))
    )
    (net (code "109") (name "/RD_4") (class "Default")
      (node (ref "U10") (pin "26") (pinfunction "R4_26") (pintype "passive"))
      (node (ref "U15") (pin "18") (pinfunction "OUT11_18") (pintype "passive"))
    )
    (net (code "110") (name "/RD_5") (class "Default")
      (node (ref "U10") (pin "24") (pinfunction "R5_24") (pintype "passive"))
      (node (ref "U15") (pin "19") (pinfunction "OUT12_19") (pintype "passive"))
    )
    (net (code "111") (name "/RD_6") (class "Default")
      (node (ref "U10") (pin "22") (pinfunction "R6_22") (pintype "passive"))
      (node (ref "U15") (pin "20") (pinfunction "OUT13_20") (pintype "passive"))
    )
    (net (code "112") (name "/RD_7") (class "Default")
      (node (ref "U10") (pin "20") (pinfunction "R7_20") (pintype "passive"))
      (node (ref "U15") (pin "21") (pinfunction "OUT14_21") (pintype "passive"))
    )
    (net (code "113") (name "/RD_8") (class "Default")
      (node (ref "U10") (pin "18") (pinfunction "R8_18") (pintype "passive"))
      (node (ref "U15") (pin "22") (pinfunction "OUT15_22") (pintype "passive"))
    )
    (net (code "114") (name "/SCLK") (class "Default")
      (node (ref "P1") (pin "3") (pinfunction "3_3") (pintype "passive"))
      (node (ref "U11") (pin "4") (pinfunction "SCLK_4") (pintype "passive"))
      (node (ref "U12") (pin "4") (pinfunction "SCLK_4") (pintype "passive"))
      (node (ref "U13") (pin "4") (pinfunction "SCLK_4") (pintype "passive"))
      (node (ref "U14") (pin "4") (pinfunction "SCLK_4") (pintype "passive"))
      (node (ref "U15") (pin "4") (pinfunction "SCLK_4") (pintype "passive"))
      (node (ref "U16") (pin "4") (pinfunction "SCLK_4") (pintype "passive"))
    )
    (net (code "115") (name "/XLAT") (class "Default")
      (node (ref "P1") (pin "6") (pinfunction "6_6") (pintype "passive"))
      (node (ref "U11") (pin "3") (pinfunction "XLAT_3") (pintype "passive"))
      (node (ref "U12") (pin "3") (pinfunction "XLAT_3") (pintype "passive"))
      (node (ref "U13") (pin "3") (pinfunction "XLAT_3") (pintype "passive"))
      (node (ref "U14") (pin "3") (pinfunction "XLAT_3") (pintype "passive"))
      (node (ref "U15") (pin "3") (pinfunction "XLAT_3") (pintype "passive"))
      (node (ref "U16") (pin "3") (pinfunction "XLAT_3") (pintype "passive"))
    )
    (net (code "116") (name "GND") (class "Default")
      (node (ref "C1") (pin "1") (pinfunction "1_1") (pintype "passive"))
      (node (ref "C10") (pin "1") (pinfunction "1_1") (pintype "passive"))
      (node (ref "C11") (pin "1") (pinfunction "1_1") (pintype "passive"))
      (node (ref "C12") (pin "1") (pinfunction "1_1") (pintype "passive"))
      (node (ref "C2") (pin "1") (pinfunction "1_1") (pintype "passive"))
      (node (ref "C21") (pin "2") (pinfunction "2_2") (pintype "passive"))
      (node (ref "C22") (pin "2") (pinfunction "2_2") (pintype "passive"))
      (node (ref "C23") (pin "2") (pinfunction "2_2") (pintype "passive"))
      (node (ref "C3") (pin "1") (pinfunction "1_1") (pintype "passive"))
      (node (ref "C4") (pin "1") (pinfunction "1_1") (pintype "passive"))
      (node (ref "C5") (pin "1") (pinfunction "1_1") (pintype "passive"))
      (node (ref "C6") (pin "1") (pinfunction "1_1") (pintype "passive"))
      (node (ref "C7") (pin "1") (pinfunction "1_1") (pintype "passive"))
      (node (ref "C8") (pin "1") (pinfunction "1_1") (pintype "passive"))
      (node (ref "C9") (pin "1") (pinfunction "1_1") (pintype "passive"))
      (node (ref "D1") (pin "2") (pinfunction "K_2") (pintype "passive"))
      (node (ref "P3") (pin "2") (pinfunction "2_2") (pintype "passive"))
      (node (ref "R1") (pin "1") (pinfunction "1_1") (pintype "passive"))
      (node (ref "R2") (pin "1") (pinfunction "1_1") (pintype "passive"))
      (node (ref "R3") (pin "1") (pinfunction "1_1") (pintype "passive"))
      (node (ref "R4") (pin "1") (pinfunction "1_1") (pintype "passive"))
      (node (ref "R5") (pin "1") (pinfunction "1_1") (pintype "passive"))
      (node (ref "R6") (pin "1") (pinfunction "1_1") (pintype "passive"))
      (node (ref "U11") (pin "1") (pinfunction "GND_1") (pintype "passive"))
      (node (ref "U12") (pin "1") (pinfunction "GND_1") (pintype "passive"))
      (node (ref "U13") (pin "1") (pinfunction "GND_1") (pintype "passive"))
      (node (ref "U14") (pin "1") (pinfunction "GND_1") (pintype "passive"))
      (node (ref "U15") (pin "1") (pinfunction "GND_1") (pintype "passive"))
      (node (ref "U16") (pin "1") (pinfunction "GND_1") (pintype "passive"))
      (node (ref "U2") (pin "4") (pinfunction "~{OE}2A_4") (pintype "input"))
      (node (ref "U2") (pin "5") (pinfunction "~{OE}2B_5") (pintype "input"))
      (node (ref "U2") (pin "8") (pinfunction "GND_8") (pintype "power_in"))
    )
    (net (code "117") (name "Net-(D1-A)") (class "Default")
      (node (ref "D1") (pin "1") (pinfunction "A_1") (pintype "passive"))
      (node (ref "R19") (pin "1") (pinfunction "1_1") (pintype "passive"))
    )
    (net (code "118") (name "Net-(I1-A)") (class "Default")
      (node (ref "I1") (pin "1") (pinfunction "A_1") (pintype "passive"))
      (node (ref "P3") (pin "1") (pinfunction "1_1") (pintype "passive"))
    )
    (net (code "119") (name "Net-(U2-~{Y}0)") (class "Default")
      (node (ref "U2") (pin "15") (pinfunction "~{Y}0_15") (pintype "output"))
      (node (ref "U3") (pin "2") (pinfunction "A_2") (pintype "passive"))
    )
    (net (code "120") (name "Net-(U2-~{Y}1)") (class "Default")
      (node (ref "U2") (pin "14") (pinfunction "~{Y}1_14") (pintype "output"))
      (node (ref "U3") (pin "4") (pinfunction "B_4") (pintype "passive"))
    )
    (net (code "121") (name "Net-(U2-~{Y}2)") (class "Default")
      (node (ref "U2") (pin "13") (pinfunction "~{Y}2_13") (pintype "output"))
      (node (ref "U4") (pin "2") (pinfunction "A_2") (pintype "passive"))
    )
    (net (code "122") (name "Net-(U2-~{Y}3)") (class "Default")
      (node (ref "U2") (pin "12") (pinfunction "~{Y}3_12") (pintype "output"))
      (node (ref "U4") (pin "4") (pinfunction "B_4") (pintype "passive"))
    )
    (net (code "123") (name "Net-(U2-~{Y}4)") (class "Default")
      (node (ref "U2") (pin "11") (pinfunction "~{Y}4_11") (pintype "output"))
      (node (ref "U5") (pin "2") (pinfunction "A_2") (pintype "passive"))
    )
    (net (code "124") (name "Net-(U2-~{Y}5)") (class "Default")
      (node (ref "U2") (pin "10") (pinfunction "~{Y}5_10") (pintype "output"))
      (node (ref "U5") (pin "4") (pinfunction "B_4") (pintype "passive"))
    )
    (net (code "125") (name "Net-(U2-~{Y}6)") (class "Default")
      (node (ref "U2") (pin "9") (pinfunction "~{Y}6_9") (pintype "output"))
      (node (ref "U6") (pin "2") (pinfunction "A_2") (pintype "passive"))
    )
    (net (code "126") (name "Net-(U2-~{Y}7)") (class "Default")
      (node (ref "U2") (pin "7") (pinfunction "~{Y}7_7") (pintype "output"))
      (node (ref "U6") (pin "4") (pinfunction "B_4") (pintype "passive"))
    )
    (net (code "127") (name "Net-(U11-IREF)") (class "Default")
      (node (ref "R1") (pin "2") (pinfunction "2_2") (pintype "passive"))
      (node (ref "U11") (pin "27") (pinfunction "IREF_27") (pintype "passive"))
    )
    (net (code "128") (name "Net-(U11-SIN)") (class "Default")
      (node (ref "U11") (pin "5") (pinfunction "SIN_5") (pintype "passive"))
      (node (ref "U12") (pin "24") (pinfunction "SOUT_24") (pintype "passive"))
    )
    (net (code "129") (name "Net-(U12-IREF)") (class "Default")
      (node (ref "R2") (pin "2") (pinfunction "2_2") (pintype "passive"))
      (node (ref "U12") (pin "27") (pinfunction "IREF_27") (pintype "passive"))
    )
    (net (code "130") (name "Net-(U12-SIN)") (class "Default")
      (node (ref "U12") (pin "5") (pinfunction "SIN_5") (pintype "passive"))
      (node (ref "U13") (pin "24") (pinfunction "SOUT_24") (pintype "passive"))
    )
    (net (code "131") (name "Net-(U13-IREF)") (class "Default")
      (node (ref "R3") (pin "2") (pinfunction "2_2") (pintype "passive"))
      (node (ref "U13") (pin "27") (pinfunction "IREF_27") (pintype "passive"))
    )
    (net (code "132") (name "Net-(U13-SIN)") (class "Default")
      (node (ref "U13") (pin "5") (pinfunction "SIN_5") (pintype "passive"))
      (node (ref "U14") (pin "24") (pinfunction "SOUT_24") (pintype "passive"))
    )
    (net (code "133") (name "Net-(U14-IREF)") (class "Default")
      (node (ref "R4") (pin "2") (pinfunction "2_2") (pintype "passive"))
      (node (ref "U14") (pin "27") (pinfunction "IREF_27") (pintype "passive"))
    )
    (net (code "134") (name "Net-(U14-SIN)") (class "Default")
      (node (ref "U14") (pin "5") (pinfunction "SIN_5") (pintype "passive"))
      (node (ref "U15") (pin "24") (pinfunction "SOUT_24") (pintype "passive"))
    )
    (net (code "135") (name "Net-(U15-IREF)") (class "Default")
      (node (ref "R5") (pin "2") (pinfunction "2_2") (pintype "passive"))
      (node (ref "U15") (pin "27") (pinfunction "IREF_27") (pintype "passive"))
    )
    (net (code "136") (name "Net-(U15-SIN)") (class "Default")
      (node (ref "U15") (pin "5") (pinfunction "SIN_5") (pintype "passive"))
      (node (ref "U16") (pin "24") (pinfunction "SOUT_24") (pintype "passive"))
    )
    (net (code "137") (name "Net-(U16-IREF)") (class "Default")
      (node (ref "R6") (pin "2") (pinfunction "2_2") (pintype "passive"))
      (node (ref "U16") (pin "27") (pinfunction "IREF_27") (pintype "passive"))
    )
    (net (code "138") (name "VCC") (class "Default")
      (node (ref "C1") (pin "2") (pinfunction "2_2") (pintype "passive"))
      (node (ref "C10") (pin "2") (pinfunction "2_2") (pintype "passive"))
      (node (ref "C11") (pin "2") (pinfunction "2_2") (pintype "passive"))
      (node (ref "C12") (pin "2") (pinfunction "2_2") (pintype "passive"))
      (node (ref "C2") (pin "2") (pinfunction "2_2") (pintype "passive"))
      (node (ref "C21") (pin "1") (pinfunction "1_1") (pintype "passive"))
      (node (ref "C22") (pin "1") (pinfunction "1_1") (pintype "passive"))
      (node (ref "C23") (pin "1") (pinfunction "1_1") (pintype "passive"))
      (node (ref "C3") (pin "2") (pinfunction "2_2") (pintype "passive"))
      (node (ref "C4") (pin "2") (pinfunction "2_2") (pintype "passive"))
      (node (ref "C5") (pin "2") (pinfunction "2_2") (pintype "passive"))
      (node (ref "C6") (pin "2") (pinfunction "2_2") (pintype "passive"))
      (node (ref "C7") (pin "2") (pinfunction "2_2") (pintype "passive"))
      (node (ref "C8") (pin "2") (pinfunction "2_2") (pintype "passive"))
      (node (ref "C9") (pin "2") (pinfunction "2_2") (pintype "passive"))
      (node (ref "I1") (pin "2") (pinfunction "K_2") (pintype "passive"))
      (node (ref "R19") (pin "2") (pinfunction "2_2") (pintype "passive"))
      (node (ref "U11") (pin "26") (pinfunction "TEST_26") (pintype "passive"))
      (node (ref "U11") (pin "28") (pinfunction "VCC_28") (pintype "passive"))
      (node (ref "U12") (pin "26") (pinfunction "TEST_26") (pintype "passive"))
      (node (ref "U12") (pin "28") (pinfunction "VCC_28") (pintype "passive"))
      (node (ref "U13") (pin "26") (pinfunction "TEST_26") (pintype "passive"))
      (node (ref "U13") (pin "28") (pinfunction "VCC_28") (pintype "passive"))
      (node (ref "U14") (pin "26") (pinfunction "TEST_26") (pintype "passive"))
      (node (ref "U14") (pin "28") (pinfunction "VCC_28") (pintype "passive"))
      (node (ref "U15") (pin "26") (pinfunction "TEST_26") (pintype "passive"))
      (node (ref "U15") (pin "28") (pinfunction "VCC_28") (pintype "passive"))
      (node (ref "U16") (pin "26") (pinfunction "TEST_26") (pintype "passive"))
      (node (ref "U16") (pin "28") (pinfunction "VCC_28") (pintype "passive"))
      (node (ref "U2") (pin "16") (pinfunction "VCC_16") (pintype "power_in"))
      (node (ref "U3") (pin "1") (pinfunction "VCC_1") (pintype "passive"))
      (node (ref "U3") (pin "3") (pinfunction "VCC_3") (pintype "passive"))
      (node (ref "U4") (pin "1") (pinfunction "VCC_1") (pintype "passive"))
      (node (ref "U4") (pin "3") (pinfunction "VCC_3") (pintype "passive"))
      (node (ref "U5") (pin "1") (pinfunction "VCC_1") (pintype "passive"))
      (node (ref "U5") (pin "3") (pinfunction "VCC_3") (pintype "passive"))
      (node (ref "U6") (pin "1") (pinfunction "VCC_1") (pintype "passive"))
      (node (ref "U6") (pin "3") (pinfunction "VCC_3") (pintype "passive"))
    )
    (net (code "139") (name "unconnected-(U11-GND-Pad29)") (class "Default")
      (node (ref "U11") (pin "29") (pinfunction "GND_29") (pintype "passive"))
    )
    (net (code "140") (name "unconnected-(U11-XERR-Pad23)") (class "Default")
      (node (ref "U11") (pin "23") (pinfunction "XERR_23") (pintype "output"))
    )
    (net (code "141") (name "unconnected-(U12-GND-Pad29)") (class "Default")
      (node (ref "U12") (pin "29") (pinfunction "GND_29") (pintype "passive"))
    )
    (net (code "142") (name "unconnected-(U12-XERR-Pad23)") (class "Default")
      (node (ref "U12") (pin "23") (pinfunction "XERR_23") (pintype "output"))
    )
    (net (code "143") (name "unconnected-(U13-GND-Pad29)") (class "Default")
      (node (ref "U13") (pin "29") (pinfunction "GND_29") (pintype "passive"))
    )
    (net (code "144") (name "unconnected-(U13-XERR-Pad23)") (class "Default")
      (node (ref "U13") (pin "23") (pinfunction "XERR_23") (pintype "output"))
    )
    (net (code "145") (name "unconnected-(U14-GND-Pad29)") (class "Default")
      (node (ref "U14") (pin "29") (pinfunction "GND_29") (pintype "passive"))
    )
    (net (code "146") (name "unconnected-(U14-XERR-Pad23)") (class "Default")
      (node (ref "U14") (pin "23") (pinfunction "XERR_23") (pintype "output"))
    )
    (net (code "147") (name "unconnected-(U15-GND-Pad29)") (class "Default")
      (node (ref "U15") (pin "29") (pinfunction "GND_29") (pintype "passive"))
    )
    (net (code "148") (name "unconnected-(U15-XERR-Pad23)") (class "Default")
      (node (ref "U15") (pin "23") (pinfunction "XERR_23") (pintype "output"))
    )
    (net (code "149") (name "unconnected-(U16-GND-Pad29)") (class "Default")
      (node (ref "U16") (pin "29") (pinfunction "GND_29") (pintype "passive"))
    )
    (net (code "150") (name "unconnected-(U16-XERR-Pad23)") (class "Default")
      (node (ref "U16") (pin "23") (pinfunction "XERR_23") (pintype "output"))
    )
  )
)
